# FunctionGenerator-ICL8038.net
KiCad netlist of a schematic drawn in EAGLE
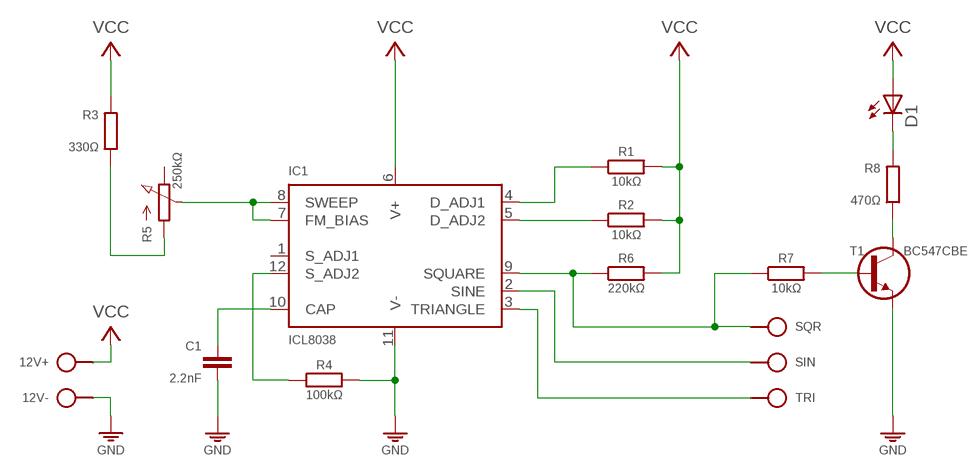
[diagram p0: schematic, sheet 1]

(export (version "E")
  (design (tool "Eeschema 10.0.6"))
  (components
    (comp (ref "12V")
      (value "SPAD+-")
      (footprint "eagle-import:SPAD-2")
      (libsource (lib "eagle-import") (part "SPAD+-"))
    )
    (comp (ref "C1")
      (value "2.2nF")
      (footprint "eagle-import:C050-020X044")
      (libsource (lib "eagle-import") (part "C050-020X044"))
    )
    (comp (ref "D1")
      (value "LED3MM")
      (footprint "eagle-import:LED3MM")
      (libsource (lib "eagle-import") (part "LED3MM"))
    )
    (comp (ref "IC1")
      (value "ICL8038")
      (footprint "eagle-import:DIL14")
      (libsource (lib "eagle-import") (part "ICL8038"))
    )
    (comp (ref "R1")
      (value "10kΩ")
      (footprint "eagle-import:0202_5")
      (libsource (lib "eagle-import") (part "R-H0202/5"))
    )
    (comp (ref "R2")
      (value "10kΩ")
      (footprint "eagle-import:0202_5")
      (libsource (lib "eagle-import") (part "R-H0202/5"))
    )
    (comp (ref "R3")
      (value "330Ω")
      (footprint "eagle-import:0202_5-V")
      (libsource (lib "eagle-import") (part "R0202/5-V"))
    )
    (comp (ref "R4")
      (value "100kΩ")
      (footprint "eagle-import:0202_5")
      (libsource (lib "eagle-import") (part "R-H0202/5"))
    )
    (comp (ref "R5")
      (value "250kΩ")
      (footprint "eagle-import:POT")
      (libsource (lib "eagle-import") (part "POT"))
    )
    (comp (ref "R6")
      (value "220kΩ")
      (footprint "eagle-import:0202_5-V")
      (libsource (lib "eagle-import") (part "R-H0202/5-V"))
    )
    (comp (ref "R7")
      (value "10kΩ")
      (footprint "eagle-import:0202_5-V")
      (libsource (lib "eagle-import") (part "R-H0202/5-V"))
    )
    (comp (ref "R8")
      (value "470Ω")
      (footprint "eagle-import:0202_5-V")
      (libsource (lib "eagle-import") (part "R0202/5-V"))
    )
    (comp (ref "SIN")
      (value "SPAD")
      (footprint "eagle-import:SPAD")
      (libsource (lib "eagle-import") (part "SPAD"))
    )
    (comp (ref "SQR")
      (value "SPAD")
      (footprint "eagle-import:SPAD")
      (libsource (lib "eagle-import") (part "SPAD"))
    )
    (comp (ref "T1")
      (value "BC547CBE")
      (footprint "eagle-import:TO92-CBE")
      (libsource (lib "eagle-import") (part "BC547CBE"))
    )
    (comp (ref "TRI")
      (value "SPAD")
      (footprint "eagle-import:SPAD")
      (libsource (lib "eagle-import") (part "SPAD"))
    )
  )
  (nets
    (net (code "1") (name "GND") (class "Default")
      (node (ref "12V") (pin "1") (pinfunction "P$1_1") (pintype "passive"))
      (node (ref "C1") (pin "2") (pinfunction "2_2") (pintype "passive"))
      (node (ref "IC1") (pin "11") (pinfunction "V-_11") (pintype "bidirectional"))
      (node (ref "R4") (pin "2") (pinfunction "2_2") (pintype "passive"))
      (node (ref "T1") (pin "E") (pinfunction "E_E") (pintype "passive"))
    )
    (net (code "2") (name "Net-(D1-C)") (class "Default")
      (node (ref "D1") (pin "K") (pinfunction "C_K") (pintype "passive"))
      (node (ref "R8") (pin "2") (pinfunction "2_2") (pintype "passive"))
    )
    (net (code "3") (name "Net-(IC1-CAP)") (class "Default")
      (node (ref "C1") (pin "1") (pinfunction "1_1") (pintype "passive"))
      (node (ref "IC1") (pin "10") (pinfunction "CAP_10") (pintype "bidirectional"))
    )
    (net (code "4") (name "Net-(IC1-D_ADJ1)") (class "Default")
      (node (ref "IC1") (pin "4") (pinfunction "D_ADJ1_4") (pintype "bidirectional"))
      (node (ref "R1") (pin "1") (pinfunction "1_1") (pintype "passive"))
    )
    (net (code "5") (name "Net-(IC1-D_ADJ2)") (class "Default")
      (node (ref "IC1") (pin "5") (pinfunction "D_ADJ2_5") (pintype "bidirectional"))
      (node (ref "R2") (pin "1") (pinfunction "1_1") (pintype "passive"))
    )
    (net (code "6") (name "Net-(IC1-FM_BIAS)") (class "Default")
      (node (ref "IC1") (pin "7") (pinfunction "FM_BIAS_7") (pintype "bidirectional"))
      (node (ref "IC1") (pin "8") (pinfunction "SWEEP_8") (pintype "bidirectional"))
      (node (ref "R5") (pin "2") (pinfunction "S_2") (pintype "passive"))
    )
    (net (code "7") (name "Net-(IC1-SINE)") (class "Default")
      (node (ref "IC1") (pin "2") (pinfunction "SINE_2") (pintype "bidirectional"))
      (node (ref "SIN") (pin "1") (pinfunction "P$1_1") (pintype "passive"))
    )
    (net (code "8") (name "Net-(IC1-SQUARE)") (class "Default")
      (node (ref "IC1") (pin "9") (pinfunction "SQUARE_9") (pintype "bidirectional"))
      (node (ref "R6") (pin "1") (pinfunction "1_1") (pintype "passive"))
      (node (ref "R7") (pin "1") (pinfunction "1_1") (pintype "passive"))
      (node (ref "SQR") (pin "1") (pinfunction "P$1_1") (pintype "passive"))
    )
    (net (code "9") (name "Net-(IC1-S_ADJ2)") (class "Default")
      (node (ref "IC1") (pin "12") (pinfunction "S_ADJ2_12") (pintype "bidirectional"))
      (node (ref "R4") (pin "1") (pinfunction "1_1") (pintype "passive"))
    )
    (net (code "10") (name "Net-(IC1-TRIANGLE)") (class "Default")
      (node (ref "IC1") (pin "3") (pinfunction "TRIANGLE_3") (pintype "bidirectional"))
      (node (ref "TRI") (pin "1") (pinfunction "P$1_1") (pintype "passive"))
    )
    (net (code "11") (name "Net-(R5-A)") (class "Default")
      (node (ref "R3") (pin "1") (pinfunction "1_1") (pintype "passive"))
      (node (ref "R5") (pin "1") (pinfunction "A_1") (pintype "passive"))
    )
    (net (code "12") (name "Net-(R7-Pad2)") (class "Default")
      (node (ref "R7") (pin "2") (pinfunction "2_2") (pintype "passive"))
      (node (ref "T1") (pin "B") (pinfunction "B_B") (pintype "passive"))
    )
    (net (code "13") (name "Net-(R8-Pad1)") (class "Default")
      (node (ref "R8") (pin "1") (pinfunction "1_1") (pintype "passive"))
      (node (ref "T1") (pin "C") (pinfunction "C_C") (pintype "passive"))
    )
    (net (code "14") (name "VCC") (class "Default")
      (node (ref "12V") (pin "2") (pinfunction "P$1_2") (pintype "passive"))
      (node (ref "D1") (pin "A") (pinfunction "A_A") (pintype "passive"))
      (node (ref "IC1") (pin "6") (pinfunction "V+_6") (pintype "bidirectional"))
      (node (ref "R1") (pin "2") (pinfunction "2_2") (pintype "passive"))
      (node (ref "R2") (pin "2") (pinfunction "2_2") (pintype "passive"))
      (node (ref "R3") (pin "2") (pinfunction "2_2") (pintype "passive"))
      (node (ref "R6") (pin "2") (pinfunction "2_2") (pintype "passive"))
    )
    (net (code "15") (name "unconnected-(IC1-S_ADJ1-Pad1)") (class "Default")
      (node (ref "IC1") (pin "1") (pinfunction "S_ADJ1_1") (pintype "bidirectional"))
    )
    (net (code "16") (name "unconnected-(R5-E-Pad3)") (class "Default")
      (node (ref "R5") (pin "3") (pinfunction "E_3") (pintype "passive"))
    )
  )
)
